# eeprom.net
KiCad netlist of a schematic drawn in Altium Designer
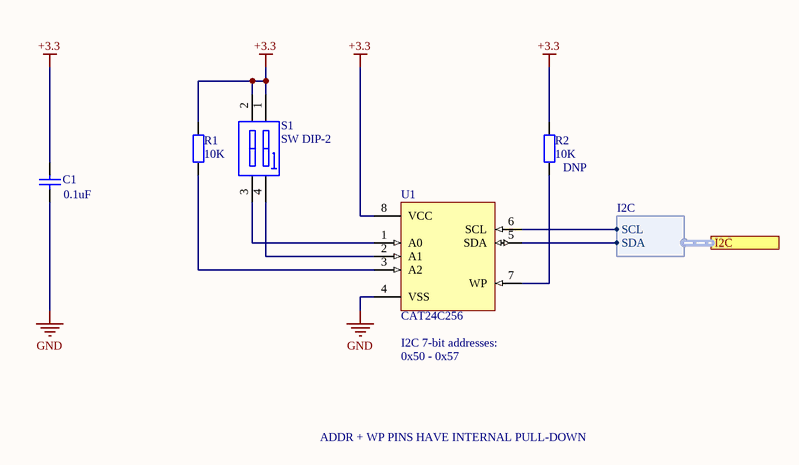
[diagram p0: eeprom.SchDoc]

(export (version "E")
  (design (tool "Eeschema 10.0.6"))
  (components
    (comp (ref "C1")
      (value "0.1uF")
      (footprint "C0603")
      (description "Capacitor")
      (fields (field (name "Comment") "Cap") (field (name "PUBLISHER") "Altium Limited"))
      (libsource (lib "Miscellaneous Devices") (part "Cap"))
    )
    (comp (ref "R1")
      (value "10K")
      (footprint "R0603")
      (description "Resistor")
      (fields (field (name "Comment") "Res2") (field (name "PUBLISHER") "Altium Limited"))
      (libsource (lib "Miscellaneous Devices") (part "Res2"))
    )
    (comp (ref "R2")
      (value "10K")
      (footprint "R0603")
      (description "Resistor")
      (fields
        (field (name "PLACE") "DNP")
        (field (name "Comment") "Res2")
        (field (name "PUBLISHER") "Altium Limited")
      )
      (libsource (lib "Miscellaneous Devices") (part "Res2"))
    )
    (comp (ref "S1")
      (value "SW DIP-2")
      (footprint "MCDHN-02F-V")
      (description "DIP Switch, 2 Position, SPST")
      (fields (field (name "PUBLISHER") "Altium Limited"))
      (libsource (lib "Miscellaneous Devices") (part "SW DIP-2"))
    )
    (comp (ref "U1")
      (value "CAT24C256")
      (footprint "CAT24C256-SOIC")
      (description "CAT24C256 256 kb I2  C CMOS Serial  EEPROM")
      (libsource (lib "CAT24C256") (part "CAT24C256"))
    )
  )
  (nets
    (net (code "2") (name "+3.3") (class "Default")
      (node (ref "C1") (pin "2") (pinfunction "2_2") (pintype "passive"))
      (node (ref "R1") (pin "2") (pinfunction "2_2") (pintype "passive"))
      (node (ref "R2") (pin "2") (pinfunction "2_2") (pintype "passive"))
      (node (ref "S1") (pin "1") (pinfunction "A1_1") (pintype "passive"))
      (node (ref "S1") (pin "2") (pinfunction "A2_2") (pintype "passive"))
      (node (ref "U1") (pin "8") (pinfunction "VCC_8") (pintype "power_in"))
    )
    (net (code "3") (name "/SCL") (class "Default")
      (node (ref "U1") (pin "6") (pinfunction "SCL_6") (pintype "input"))
    )
    (net (code "4") (name "/SDA") (class "Default")
      (node (ref "U1") (pin "5") (pinfunction "SDA_5") (pintype "bidirectional"))
    )
    (net (code "6") (name "GND") (class "Default")
      (node (ref "C1") (pin "1") (pinfunction "1_1") (pintype "passive"))
      (node (ref "U1") (pin "4") (pinfunction "VSS_4") (pintype "power_in"))
    )
    (net (code "7") (name "Net-(S1-B1)") (class "Default")
      (node (ref "S1") (pin "4") (pinfunction "B1_4") (pintype "passive"))
      (node (ref "U1") (pin "2") (pinfunction "A1_2") (pintype "input"))
    )
    (net (code "8") (name "Net-(S1-B2)") (class "Default")
      (node (ref "S1") (pin "3") (pinfunction "B2_3") (pintype "passive"))
      (node (ref "U1") (pin "1") (pinfunction "A0_1") (pintype "input"))
    )
    (net (code "9") (name "Net-(U1-A2)") (class "Default")
      (node (ref "R1") (pin "1") (pinfunction "1_1") (pintype "passive"))
      (node (ref "U1") (pin "3") (pinfunction "A2_3") (pintype "input"))
    )
    (net (code "10") (name "Net-(U1-WP)") (class "Default")
      (node (ref "R2") (pin "1") (pinfunction "1_1") (pintype "passive"))
      (node (ref "U1") (pin "7") (pinfunction "WP_7") (pintype "input"))
    )
  )
)
